# Control_Interface.net
KiCad netlist of a schematic drawn in Altium Designer
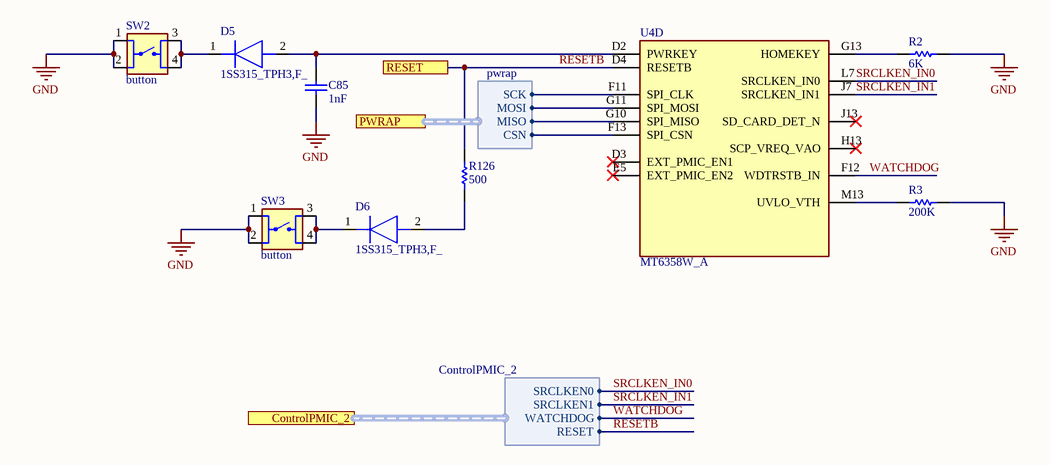
[diagram p0: Control_Interface.SchDoc]

(export (version "E")
  (design (tool "Eeschema 10.0.6"))
  (components
    (comp (ref "C85")
      (value "1nF")
      (footprint "C0603")
      (fields (field (name "Comment") "C0603"))
      (libsource (lib "kit") (part "C0603"))
    )
    (comp (ref "D5")
      (value "1SS315_TPH3,F_")
      (footprint "hello:SOD2513X110N")
      (description "Diode")
      (fields (field (name "MANUFACTURER_PART_NUMBER") "1SS315(TPH3,F)"))
      (libsource (lib "*") (part "1SS315_TPH3,F_"))
    )
    (comp (ref "D6")
      (value "1SS315_TPH3,F_")
      (footprint "hello:SOD2513X110N")
      (description "Diode")
      (fields (field (name "MANUFACTURER_PART_NUMBER") "1SS315(TPH3,F)"))
      (libsource (lib "*") (part "1SS315_TPH3,F_"))
    )
    (comp (ref "R2")
      (value "6K")
      (footprint "R0603")
      (fields (field (name "Comment") "R0603"))
      (libsource (lib "kit") (part "R0603"))
    )
    (comp (ref "R3")
      (value "200K")
      (footprint "R0603")
      (fields (field (name "Comment") "R0603"))
      (libsource (lib "kit") (part "R0603"))
    )
    (comp (ref "R126")
      (value "500")
      (footprint "R0603")
      (fields (field (name "Comment") "R0603"))
      (libsource (lib "kit") (part "R0603"))
    )
    (comp (ref "SW2")
      (value "button")
      (footprint "BUTTON")
      (description "6x6 mm")
      (libsource (lib "kit") (part "button"))
    )
    (comp (ref "SW3")
      (value "button")
      (footprint "BUTTON")
      (description "6x6 mm")
      (libsource (lib "kit") (part "button"))
    )
    (comp (ref "U4")
      (value "MT6358W_A")
      (footprint "BGA194C40P16X15_640X600X66")
      (description "Integrated Circuit")
      (fields
        (field (name "MANUFACTURER_PART_NUMBER") "MT6358W/A")
        (field (name "MOUSER PART NUMBER") "840-MT6358W/A")
      )
      (libsource (lib "kit") (part "MT6358W_A"))
    )
  )
  (nets
    (net (code "3") (name "/CSN") (class "Default")
      (node (ref "U4") (pin "F13") (pinfunction "SPI_CSN_F13") (pintype "passive"))
    )
    (net (code "4") (name "/MISO") (class "Default")
      (node (ref "U4") (pin "G10") (pinfunction "SPI_MISO_G10") (pintype "passive"))
    )
    (net (code "5") (name "/MOSI") (class "Default")
      (node (ref "U4") (pin "G11") (pinfunction "SPI_MOSI_G11") (pintype "passive"))
    )
    (net (code "6") (name "/RESETB") (class "Default")
      (node (ref "R126") (pin "2") (pinfunction "2_2") (pintype "passive"))
      (node (ref "U4") (pin "D4") (pinfunction "RESETB_D4") (pintype "passive"))
    )
    (net (code "7") (name "/SCK") (class "Default")
      (node (ref "U4") (pin "F11") (pinfunction "SPI_CLK_F11") (pintype "passive"))
    )
    (net (code "8") (name "/SRCLKEN_IN0") (class "Default")
      (node (ref "U4") (pin "L7") (pinfunction "SRCLKEN_IN0_L7") (pintype "passive"))
    )
    (net (code "9") (name "/SRCLKEN_IN1") (class "Default")
      (node (ref "U4") (pin "J7") (pinfunction "SRCLKEN_IN1_J7") (pintype "passive"))
    )
    (net (code "10") (name "/WATCHDOG") (class "Default")
      (node (ref "U4") (pin "F12") (pinfunction "WDTRSTB_IN_F12") (pintype "passive"))
    )
    (net (code "13") (name "GND") (class "Default")
      (node (ref "C85") (pin "1") (pinfunction "1_1") (pintype "passive"))
      (node (ref "R2") (pin "2") (pinfunction "2_2") (pintype "passive"))
      (node (ref "R3") (pin "2") (pinfunction "2_2") (pintype "passive"))
      (node (ref "SW2") (pin "1") (pinfunction "1_1") (pintype "passive"))
      (node (ref "SW2") (pin "2") (pinfunction "2_2") (pintype "passive"))
      (node (ref "SW3") (pin "1") (pinfunction "1_1") (pintype "passive"))
      (node (ref "SW3") (pin "2") (pinfunction "2_2") (pintype "passive"))
    )
    (net (code "14") (name "Net-(D5-A)") (class "Default")
      (node (ref "C85") (pin "2") (pinfunction "2_2") (pintype "passive"))
      (node (ref "D5") (pin "2") (pinfunction "A_2") (pintype "passive"))
      (node (ref "U4") (pin "D2") (pinfunction "PWRKEY_D2") (pintype "passive"))
    )
    (net (code "15") (name "Net-(D5-K)") (class "Default")
      (node (ref "D5") (pin "1") (pinfunction "K_1") (pintype "passive"))
      (node (ref "SW2") (pin "3") (pinfunction "3_3") (pintype "passive"))
      (node (ref "SW2") (pin "4") (pinfunction "4_4") (pintype "passive"))
    )
    (net (code "16") (name "Net-(D6-A)") (class "Default")
      (node (ref "D6") (pin "2") (pinfunction "A_2") (pintype "passive"))
      (node (ref "R126") (pin "1") (pinfunction "1_1") (pintype "passive"))
    )
    (net (code "17") (name "Net-(D6-K)") (class "Default")
      (node (ref "D6") (pin "1") (pinfunction "K_1") (pintype "passive"))
      (node (ref "SW3") (pin "3") (pinfunction "3_3") (pintype "passive"))
      (node (ref "SW3") (pin "4") (pinfunction "4_4") (pintype "passive"))
    )
    (net (code "18") (name "Net-(U4D-HOMEKEY)") (class "Default")
      (node (ref "R2") (pin "1") (pinfunction "1_1") (pintype "passive"))
      (node (ref "U4") (pin "G13") (pinfunction "HOMEKEY_G13") (pintype "passive"))
    )
    (net (code "19") (name "Net-(U4D-UVLO_VTH)") (class "Default")
      (node (ref "R3") (pin "1") (pinfunction "1_1") (pintype "passive"))
      (node (ref "U4") (pin "M13") (pinfunction "UVLO_VTH_M13") (pintype "passive"))
    )
    (net (code "20") (name "unconnected-(U4D-EXT_PMIC_EN1-PadD3)") (class "Default")
      (node (ref "U4") (pin "D3") (pinfunction "EXT_PMIC_EN1_D3") (pintype "passive+no_connect"))
    )
    (net (code "21") (name "unconnected-(U4D-EXT_PMIC_EN2-PadE5)") (class "Default")
      (node (ref "U4") (pin "E5") (pinfunction "EXT_PMIC_EN2_E5") (pintype "passive+no_connect"))
    )
    (net (code "22") (name "unconnected-(U4D-SCP_VREQ_VAO-PadH13)") (class "Default")
      (node (ref "U4") (pin "H13") (pinfunction "SCP_VREQ_VAO_H13") (pintype "passive+no_connect"))
    )
    (net (code "23") (name "unconnected-(U4D-SD_CARD_DET_N-PadJ13)") (class "Default")
      (node (ref "U4") (pin "J13") (pinfunction "SD_CARD_DET_N_J13") (pintype "passive+no_connect"))
    )
  )
)
